# updatedLoraXbee.net
KiCad netlist of a schematic drawn in Altium Designer
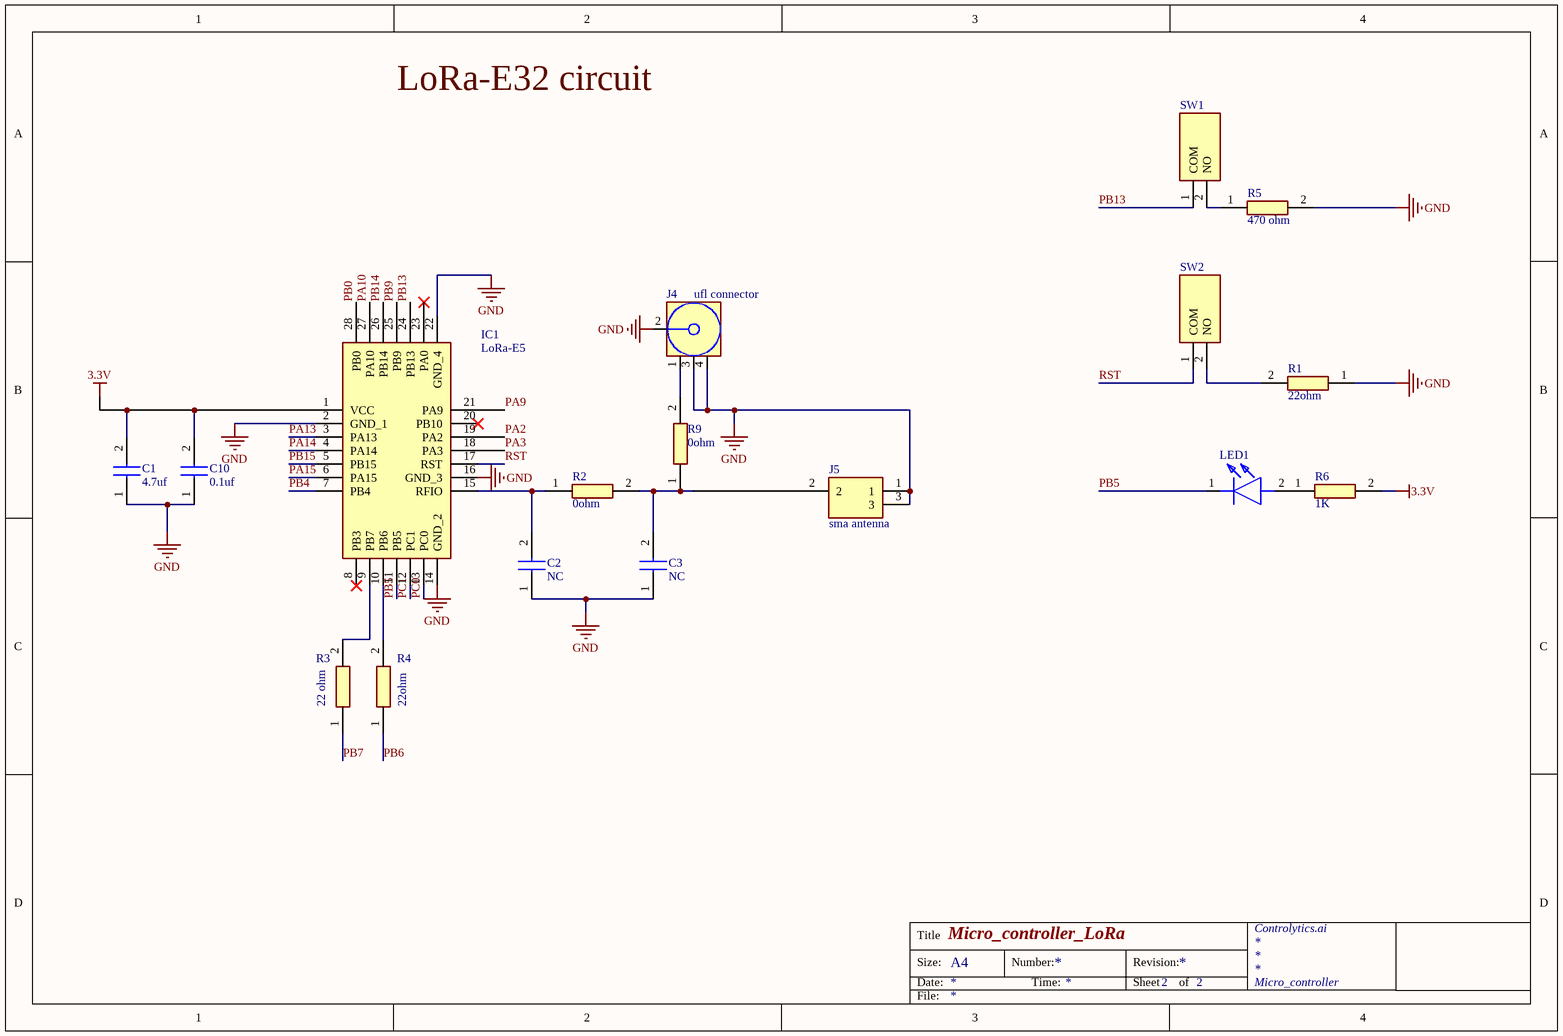
[diagram p0: updatedLoraXbee.SchDoc]

(export (version "E")
  (design (tool "Eeschema 10.0.6"))
  (components
    (comp (ref "C1")
      (value "4.7uf")
      (footprint "SamacSys:CAPC1608X100N")
      (description "Capacitor")
      (fields
        (field (name "MANUFACTURER_PART_NUMBER") "GCJ188C70J475KE02D")
        (field (name "MOUSER PART NUMBER") "81-GCJ188C70J475KE2D")
      )
      (libsource (lib "SamacSys") (part "GCJ188C70J475KE02D"))
    )
    (comp (ref "C2")
      (value "NC")
      (footprint "SamacSys:CAPC1608X90N")
      (description "Capacitor")
      (fields
        (field (name "MANUFACTURER_PART_NUMBER") "GRM188R71C104MA01D")
        (field (name "MOUSER PART NUMBER") "81-GRM18R71C104MA01D")
      )
      (libsource (lib "SamacSys") (part "GRM188R71C104MA01D"))
    )
    (comp (ref "C3")
      (value "NC")
      (footprint "SamacSys:CAPC1608X90N")
      (description "Capacitor")
      (fields
        (field (name "MANUFACTURER_PART_NUMBER") "GRM188R71C104MA01D")
        (field (name "MOUSER PART NUMBER") "81-GRM18R71C104MA01D")
      )
      (libsource (lib "SamacSys") (part "GRM188R71C104MA01D"))
    )
    (comp (ref "C10")
      (value "0.1uf")
      (footprint "SamacSys:CAPC1608X100N")
      (description "Capacitor")
      (fields
        (field (name "MANUFACTURER_PART_NUMBER") "GCJ188C70J475KE02D")
        (field (name "MOUSER PART NUMBER") "81-GCJ188C70J475KE2D")
      )
      (libsource (lib "SamacSys") (part "GCJ188C70J475KE02D"))
    )
    (comp (ref "IC1")
      (value "LoRa-E5")
      (footprint "SamacSys:LoRaE5")
      (description "Integrated Circuit")
      (libsource (lib "*") (part "LoRa-E5"))
    )
    (comp (ref "J4")
      (value "ufl connector")
      (footprint "SMA_EDGE_5_6.4x7.8")
      (libsource (lib "Symbol") (part "SMA_CON_4"))
    )
    (comp (ref "J5")
      (value "sma antenna")
      (footprint "1909763-1")
      (description "Connector")
      (fields
        (field (name "MANUFACTURER_PART_NUMBER") "1909763-1")
        (field (name "MOUSER PART NUMBER") "571-1909763-1")
      )
      (libsource (lib "Symbol") (part "1909763-1"))
    )
    (comp (ref "LED1")
      (value "FKR1111C-TR")
      (footprint "LED-0603-BLUE")
      (description "LED")
      (fields (field (name "MOUSER PART NUMBER") "327-FKR1111CTR"))
      (libsource (lib "SamacSys") (part "FKR1111C-TR"))
    )
    (comp (ref "R1")
      (value "22ohm")
      (footprint "SamacSys:RESC1609X55N")
      (description "Resistor")
      (fields
        (field (name "MANUFACTURER_PART_NUMBER") "ERJ-P03J220V")
        (field (name "MOUSER PART NUMBER") "667-ERJ-P03J220V")
      )
      (libsource (lib "SamacSys") (part "ERJ-P03J220V"))
    )
    (comp (ref "R2")
      (value "0ohm")
      (footprint "SamacSys:RESC1608X55N")
      (description "Resistor")
      (fields
        (field (name "MANUFACTURER_PART_NUMBER") "MCT0603HZ0000ZP500")
        (field (name "MOUSER PART NUMBER") "594-MCT0603HZ0000ZP5")
      )
      (libsource (lib "") (part "MCT0603HZ0000ZP500_1"))
    )
    (comp (ref "R3")
      (value "22 ohm")
      (footprint "SamacSys:RESC1609X55N")
      (description "Resistor")
      (fields
        (field (name "MANUFACTURER_PART_NUMBER") "ERJ-P03J220V")
        (field (name "MOUSER PART NUMBER") "667-ERJ-P03J220V")
      )
      (libsource (lib "") (part "ERJ-P03J220V_1"))
    )
    (comp (ref "R4")
      (value "22ohm")
      (footprint "SamacSys:RESC1609X55N")
      (description "Resistor")
      (fields
        (field (name "MANUFACTURER_PART_NUMBER") "ERJ-P03J220V")
        (field (name "MOUSER PART NUMBER") "667-ERJ-P03J220V")
      )
      (libsource (lib "") (part "ERJ-P03J220V_1"))
    )
    (comp (ref "R5")
      (value "470 ohm")
      (footprint "SamacSys:RESC1608X55N")
      (description "Resistor")
      (fields
        (field (name "MANUFACTURER_PART_NUMBER") "ERJ-S03F4700V")
        (field (name "MOUSER PART NUMBER") "667-ERJ-S03F4700V")
      )
      (libsource (lib "SamacSys") (part "ERJ-S03F4700V"))
    )
    (comp (ref "R6")
      (value "1K")
      (footprint "SamacSys:ERA3AEB101V")
      (description "Resistor")
      (fields
        (field (name "MANUFACTURER_PART_NUMBER") "ERA-3AED102V")
        (field (name "MOUSER PART NUMBER") "667-ERA-3AED102V")
      )
      (libsource (lib "SamacSys") (part "ERA-3AED102V"))
    )
    (comp (ref "R9")
      (value "0ohm")
      (footprint "SamacSys:RESC1608X55N")
      (description "Resistor")
      (fields
        (field (name "MANUFACTURER_PART_NUMBER") "MCT0603HZ0000ZP500")
        (field (name "MOUSER PART NUMBER") "594-MCT0603HZ0000ZP5")
      )
      (libsource (lib "SamacSys") (part "MCT0603HZ0000ZP500"))
    )
    (comp (ref "SW1")
      (value "PTS636_SK25F_SMTR_LFS")
      (footprint "PTS636SK25FSMTRLFS")
      (description "Switch")
      (fields
        (field (name "MANUFACTURER_PART_NUMBER") "PTS636 SK25F SMTR LFS")
        (field (name "MOUSER PART NUMBER") "611-PTS636SK25FSMTRL")
      )
      (libsource (lib "CONTROLYTICS") (part "SW1_PTS636_SK25F_SMTR_LFS-SMT"))
    )
    (comp (ref "SW2")
      (value "PTS636_SK25F_SMTR_LFS")
      (footprint "PTS636SK25FSMTRLFS")
      (description "Switch")
      (fields
        (field (name "MANUFACTURER_PART_NUMBER") "PTS636 SK25F SMTR LFS")
        (field (name "MOUSER PART NUMBER") "611-PTS636SK25FSMTRL")
      )
      (libsource (lib "CONTROLYTICS") (part "SW1_PTS636_SK25F_SMTR_LFS-SMT"))
    )
  )
  (nets
    (net (code "1") (name "/PA2") (class "Default")
      (node (ref "IC1") (pin "19") (pinfunction "PA2_19") (pintype "passive"))
    )
    (net (code "2") (name "/PA3") (class "Default")
      (node (ref "IC1") (pin "18") (pinfunction "PA3_18") (pintype "passive"))
    )
    (net (code "3") (name "/PA9") (class "Default")
      (node (ref "IC1") (pin "21") (pinfunction "PA9_21") (pintype "passive"))
    )
    (net (code "4") (name "/PA10") (class "Default")
      (node (ref "IC1") (pin "27") (pinfunction "PA10_27") (pintype "passive"))
    )
    (net (code "5") (name "/PA13") (class "Default")
      (node (ref "IC1") (pin "3") (pinfunction "PA13_3") (pintype "passive"))
    )
    (net (code "6") (name "/PA14") (class "Default")
      (node (ref "IC1") (pin "4") (pinfunction "PA14_4") (pintype "passive"))
    )
    (net (code "7") (name "/PA15") (class "Default")
      (node (ref "IC1") (pin "6") (pinfunction "PA15_6") (pintype "passive"))
    )
    (net (code "8") (name "/PB0") (class "Default")
      (node (ref "IC1") (pin "28") (pinfunction "PB0_28") (pintype "passive"))
    )
    (net (code "9") (name "/PB4") (class "Default")
      (node (ref "IC1") (pin "7") (pinfunction "PB4_7") (pintype "passive"))
    )
    (net (code "10") (name "/PB5") (class "Default")
      (node (ref "IC1") (pin "11") (pinfunction "PB5_11") (pintype "passive"))
      (node (ref "LED1") (pin "1") (pinfunction "K_1") (pintype "passive"))
    )
    (net (code "11") (name "/PB6") (class "Default")
      (node (ref "R4") (pin "1") (pinfunction "1_1") (pintype "passive"))
    )
    (net (code "12") (name "/PB7") (class "Default")
      (node (ref "R3") (pin "1") (pinfunction "1_1") (pintype "passive"))
    )
    (net (code "13") (name "/PB9") (class "Default")
      (node (ref "IC1") (pin "25") (pinfunction "PB9_25") (pintype "passive"))
    )
    (net (code "14") (name "/PB13") (class "Default")
      (node (ref "IC1") (pin "24") (pinfunction "PB13_24") (pintype "passive"))
      (node (ref "SW1") (pin "1") (pinfunction "COM_1") (pintype "passive"))
    )
    (net (code "15") (name "/PB14") (class "Default")
      (node (ref "IC1") (pin "26") (pinfunction "PB14_26") (pintype "passive"))
    )
    (net (code "16") (name "/PB15") (class "Default")
      (node (ref "IC1") (pin "5") (pinfunction "PB15_5") (pintype "passive"))
    )
    (net (code "17") (name "/PC0") (class "Default")
      (node (ref "IC1") (pin "13") (pinfunction "PC0_13") (pintype "passive"))
    )
    (net (code "18") (name "/PC1") (class "Default")
      (node (ref "IC1") (pin "12") (pinfunction "PC1_12") (pintype "passive"))
    )
    (net (code "19") (name "/RST") (class "Default")
      (node (ref "IC1") (pin "17") (pinfunction "RST_17") (pintype "passive"))
      (node (ref "SW2") (pin "1") (pinfunction "COM_1") (pintype "passive"))
    )
    (net (code "20") (name "3.3V") (class "Default")
      (node (ref "C1") (pin "2") (pinfunction "2_2") (pintype "passive"))
      (node (ref "C10") (pin "2") (pinfunction "2_2") (pintype "passive"))
      (node (ref "IC1") (pin "1") (pinfunction "VCC_1") (pintype "passive"))
      (node (ref "R6") (pin "2") (pinfunction "2_2") (pintype "passive"))
    )
    (net (code "21") (name "GND") (class "Default")
      (node (ref "C1") (pin "1") (pinfunction "1_1") (pintype "passive"))
      (node (ref "C10") (pin "1") (pinfunction "1_1") (pintype "passive"))
      (node (ref "C2") (pin "1") (pinfunction "1_1") (pintype "passive"))
      (node (ref "C3") (pin "1") (pinfunction "1_1") (pintype "passive"))
      (node (ref "IC1") (pin "14") (pinfunction "GND_2_14") (pintype "passive"))
      (node (ref "IC1") (pin "16") (pinfunction "GND_3_16") (pintype "passive"))
      (node (ref "IC1") (pin "2") (pinfunction "GND_1_2") (pintype "passive"))
      (node (ref "IC1") (pin "22") (pinfunction "GND_4_22") (pintype "passive"))
      (node (ref "J4") (pin "2") (pinfunction "Signal_2") (pintype "passive"))
      (node (ref "J4") (pin "3") (pinfunction "GND_3") (pintype "power_in"))
      (node (ref "J4") (pin "4") (pinfunction "GND_4") (pintype "power_in"))
      (node (ref "J5") (pin "1") (pinfunction "1_1") (pintype "passive"))
      (node (ref "J5") (pin "3") (pinfunction "3_3") (pintype "passive"))
      (node (ref "R1") (pin "1") (pinfunction "1_1") (pintype "passive"))
      (node (ref "R5") (pin "2") (pinfunction "2_2") (pintype "passive"))
    )
    (net (code "22") (name "Net-(C3-Pad2)") (class "Default")
      (node (ref "C3") (pin "2") (pinfunction "2_2") (pintype "passive"))
      (node (ref "J5") (pin "2") (pinfunction "2_2") (pintype "passive"))
      (node (ref "R2") (pin "2") (pinfunction "2_2") (pintype "passive"))
      (node (ref "R9") (pin "1") (pinfunction "1_1") (pintype "passive"))
    )
    (net (code "23") (name "Net-(IC1-PB6)") (class "Default")
      (node (ref "IC1") (pin "10") (pinfunction "PB6_10") (pintype "passive"))
      (node (ref "R4") (pin "2") (pinfunction "2_2") (pintype "passive"))
    )
    (net (code "24") (name "Net-(IC1-PB7)") (class "Default")
      (node (ref "IC1") (pin "9") (pinfunction "PB7_9") (pintype "passive"))
      (node (ref "R3") (pin "2") (pinfunction "2_2") (pintype "passive"))
    )
    (net (code "25") (name "Net-(IC1-RFIO)") (class "Default")
      (node (ref "C2") (pin "2") (pinfunction "2_2") (pintype "passive"))
      (node (ref "IC1") (pin "15") (pinfunction "RFIO_15") (pintype "passive"))
      (node (ref "R2") (pin "1") (pinfunction "1_1") (pintype "passive"))
    )
    (net (code "26") (name "Net-(J4-GND-Pad1)") (class "Default")
      (node (ref "J4") (pin "1") (pinfunction "GND_1") (pintype "power_in"))
      (node (ref "R9") (pin "2") (pinfunction "2_2") (pintype "passive"))
    )
    (net (code "27") (name "Net-(LED1-A)") (class "Default")
      (node (ref "LED1") (pin "2") (pinfunction "A_2") (pintype "passive"))
      (node (ref "R6") (pin "1") (pinfunction "1_1") (pintype "passive"))
    )
    (net (code "28") (name "Net-(SW1-NO)") (class "Default")
      (node (ref "R5") (pin "1") (pinfunction "1_1") (pintype "passive"))
      (node (ref "SW1") (pin "2") (pinfunction "NO_2") (pintype "passive"))
    )
    (net (code "29") (name "Net-(SW2-NO)") (class "Default")
      (node (ref "R1") (pin "2") (pinfunction "2_2") (pintype "passive"))
      (node (ref "SW2") (pin "2") (pinfunction "NO_2") (pintype "passive"))
    )
    (net (code "30") (name "unconnected-(IC1-PA0-Pad23)") (class "Default")
      (node (ref "IC1") (pin "23") (pinfunction "PA0_23") (pintype "passive+no_connect"))
    )
    (net (code "31") (name "unconnected-(IC1-PB3-Pad8)") (class "Default")
      (node (ref "IC1") (pin "8") (pinfunction "PB3_8") (pintype "passive+no_connect"))
    )
    (net (code "32") (name "unconnected-(IC1-PB10-Pad20)") (class "Default")
      (node (ref "IC1") (pin "20") (pinfunction "PB10_20") (pintype "passive+no_connect"))
    )
  )
)
